# ev_ver_3.net
KiCad netlist of a schematic drawn in EAGLE
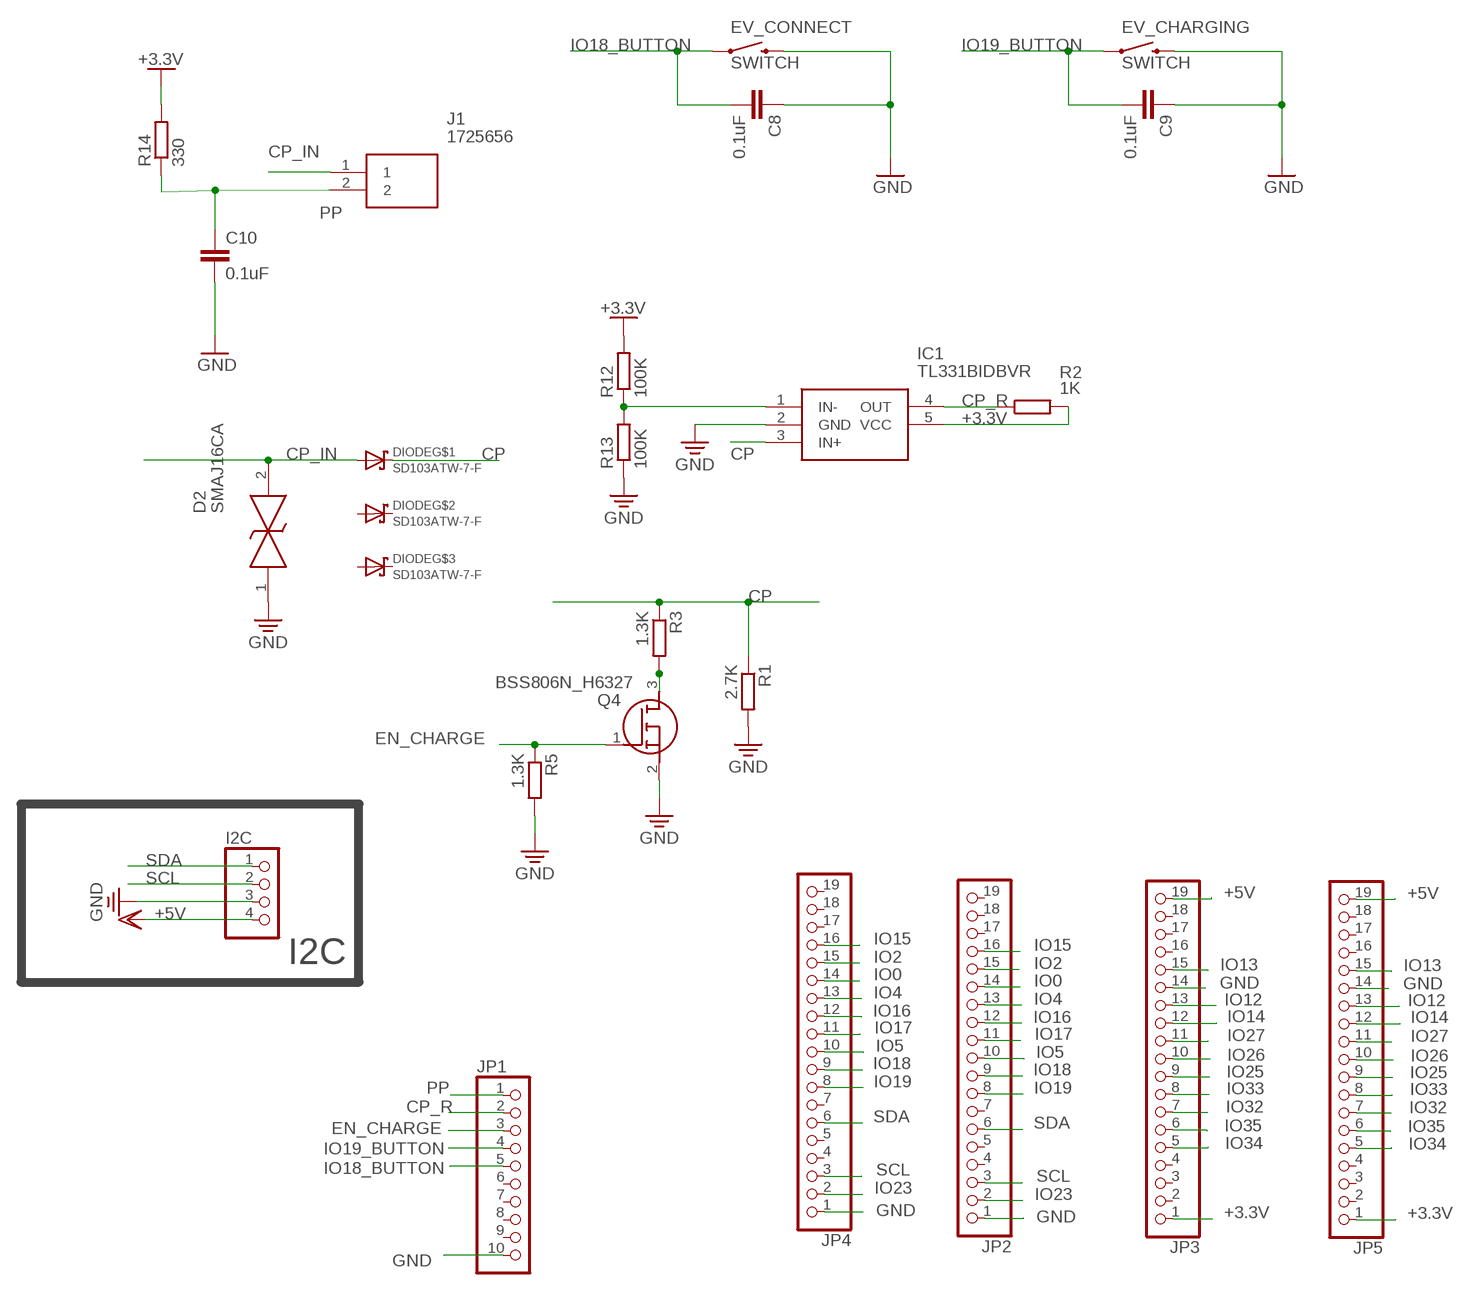
[diagram p0: schematic, sheet 1]

(export (version "E")
  (design (tool "Eeschema 10.0.6"))
  (components
    (comp (ref "C8")
      (value "0.1uF")
      (footprint "eagle-import:C0805")
      (libsource (lib "eagle-import") (part "C-EUC0805"))
    )
    (comp (ref "C9")
      (value "0.1uF")
      (footprint "eagle-import:C0805")
      (libsource (lib "eagle-import") (part "C-EUC0805"))
    )
    (comp (ref "C10")
      (value "0.1uF")
      (footprint "eagle-import:C0805")
      (libsource (lib "eagle-import") (part "C-EUC0805"))
    )
    (comp (ref "D2")
      (value "SMAJ16CA")
      (footprint "eagle-import:DIOM6626X229N")
      (fields (field (name "MOUSER_PART_NUMBER") "576-SMAJ16CA"))
      (libsource (lib "eagle-import") (part "SMAJ16CA"))
    )
    (comp (ref "DIODE")
      (value "SD103ATW-7-F")
      (footprint "eagle-import:SOT363")
      (fields (field (name "MF") "Diodes Inc."))
      (libsource (lib "eagle-import") (part "SD103ATW-7-F"))
    )
    (comp (ref "EV_CHARGING")
      (value "SWITCH")
      (footprint "eagle-import:SWITCH_2PIN")
      (libsource (lib "eagle-import") (part "SWITCH"))
    )
    (comp (ref "EV_CONNECT")
      (value "SWITCH")
      (footprint "eagle-import:SWITCH_2PIN")
      (libsource (lib "eagle-import") (part "SWITCH"))
    )
    (comp (ref "I2C")
      (value "PINHD-1X4")
      (footprint "eagle-import:1X04")
      (libsource (lib "eagle-import") (part "PINHD-1X4"))
    )
    (comp (ref "IC1")
      (value "TL331BIDBVR")
      (footprint "eagle-import:SOT95P280X145-5N")
      (fields (field (name "MOUSER_PART_NUMBER") "595-TL331BIDBVR"))
      (libsource (lib "eagle-import") (part "TL331BIDBVR"))
    )
    (comp (ref "J1")
      (value "1725656")
      (footprint "eagle-import:1725656")
      (fields (field (name "MOUSER_PART_NUMBER") "651-1725656"))
      (libsource (lib "eagle-import") (part "1725656"))
    )
    (comp (ref "JP1")
      (value "PINHD-1X10")
      (footprint "eagle-import:1X10")
      (libsource (lib "eagle-import") (part "PINHD-1X10"))
    )
    (comp (ref "JP2")
      (value "PINHD-1X19")
      (footprint "eagle-import:1X19")
      (libsource (lib "eagle-import") (part "PINHD-1X19"))
    )
    (comp (ref "JP3")
      (value "PINHD-1X19")
      (footprint "eagle-import:1X19")
      (libsource (lib "eagle-import") (part "PINHD-1X19"))
    )
    (comp (ref "JP4")
      (value "PINHD-1X19")
      (footprint "eagle-import:1X19")
      (libsource (lib "eagle-import") (part "PINHD-1X19"))
    )
    (comp (ref "JP5")
      (value "PINHD-1X19")
      (footprint "eagle-import:1X19")
      (libsource (lib "eagle-import") (part "PINHD-1X19"))
    )
    (comp (ref "Q4")
      (value "BSS806N_H6327")
      (footprint "eagle-import:SOT95P240X110-3N")
      (fields
        (field (name "MANUFACTURER_PART_NUMBER") "BSS806N H6327")
        (field (name "MOUSER_PART_NUMBER") "726-BSS806NH6327XT")
      )
      (libsource (lib "eagle-import") (part "BSS806N_H6327"))
    )
    (comp (ref "R1")
      (value "2.7K")
      (footprint "eagle-import:R0805")
      (libsource (lib "eagle-import") (part "R-EU_R0805"))
    )
    (comp (ref "R2")
      (value "1K")
      (footprint "eagle-import:R0805")
      (libsource (lib "eagle-import") (part "R-EU_R0805"))
    )
    (comp (ref "R3")
      (value "1.3K")
      (footprint "eagle-import:R0805")
      (libsource (lib "eagle-import") (part "R-EU_R0805"))
    )
    (comp (ref "R5")
      (value "1.3K")
      (footprint "eagle-import:R0805")
      (libsource (lib "eagle-import") (part "R-EU_R0805"))
    )
    (comp (ref "R12")
      (value "100K")
      (footprint "eagle-import:R0805")
      (libsource (lib "eagle-import") (part "R-EU_R0805"))
    )
    (comp (ref "R13")
      (value "100K")
      (footprint "eagle-import:R0805")
      (libsource (lib "eagle-import") (part "R-EU_R0805"))
    )
    (comp (ref "R14")
      (value "330")
      (footprint "eagle-import:R0805")
      (libsource (lib "eagle-import") (part "R-EU_R0805"))
    )
  )
  (nets
    (net (code "1") (name "+3.3V") (class "Default")
      (node (ref "IC1") (pin "5") (pinfunction "VCC_5") (pintype "bidirectional"))
      (node (ref "JP3") (pin "1") (pinfunction "1_1") (pintype "passive"))
      (node (ref "JP5") (pin "1") (pinfunction "1_1") (pintype "passive"))
      (node (ref "R12") (pin "2") (pinfunction "2_2") (pintype "passive"))
      (node (ref "R14") (pin "2") (pinfunction "2_2") (pintype "passive"))
      (node (ref "R2") (pin "2") (pinfunction "2_2") (pintype "passive"))
    )
    (net (code "2") (name "/CP") (class "Default")
      (node (ref "DIODE") (pin "1") (pinfunction "C_1") (pintype "passive"))
      (node (ref "IC1") (pin "3") (pinfunction "IN+_3") (pintype "bidirectional"))
      (node (ref "R1") (pin "1") (pinfunction "1_1") (pintype "passive"))
      (node (ref "R3") (pin "1") (pinfunction "1_1") (pintype "passive"))
    )
    (net (code "3") (name "/CP_IN") (class "Default")
      (node (ref "D2") (pin "2") (pinfunction "2_2") (pintype "bidirectional"))
      (node (ref "DIODE") (pin "6") (pinfunction "A_6") (pintype "passive"))
      (node (ref "J1") (pin "1") (pinfunction "1_1") (pintype "bidirectional"))
    )
    (net (code "4") (name "/CP_R") (class "Default")
      (node (ref "IC1") (pin "4") (pinfunction "OUT_4") (pintype "bidirectional"))
      (node (ref "JP1") (pin "2") (pinfunction "2_2") (pintype "passive"))
      (node (ref "R2") (pin "1") (pinfunction "1_1") (pintype "passive"))
    )
    (net (code "5") (name "/EN_CHARGE") (class "Default")
      (node (ref "JP1") (pin "3") (pinfunction "3_3") (pintype "passive"))
      (node (ref "Q4") (pin "1") (pinfunction "G_1") (pintype "bidirectional"))
      (node (ref "R5") (pin "1") (pinfunction "1_1") (pintype "passive"))
    )
    (net (code "6") (name "/IO0") (class "Default")
      (node (ref "JP2") (pin "14") (pinfunction "14_14") (pintype "passive"))
      (node (ref "JP4") (pin "14") (pinfunction "14_14") (pintype "passive"))
    )
    (net (code "7") (name "/IO2") (class "Default")
      (node (ref "JP2") (pin "15") (pinfunction "15_15") (pintype "passive"))
      (node (ref "JP4") (pin "15") (pinfunction "15_15") (pintype "passive"))
    )
    (net (code "8") (name "/IO4") (class "Default")
      (node (ref "JP2") (pin "13") (pinfunction "13_13") (pintype "passive"))
      (node (ref "JP4") (pin "13") (pinfunction "13_13") (pintype "passive"))
    )
    (net (code "9") (name "/IO5") (class "Default")
      (node (ref "JP2") (pin "10") (pinfunction "10_10") (pintype "passive"))
      (node (ref "JP4") (pin "10") (pinfunction "10_10") (pintype "passive"))
    )
    (net (code "10") (name "/IO12") (class "Default")
      (node (ref "JP3") (pin "13") (pinfunction "13_13") (pintype "passive"))
      (node (ref "JP5") (pin "13") (pinfunction "13_13") (pintype "passive"))
    )
    (net (code "11") (name "/IO13") (class "Default")
      (node (ref "JP3") (pin "15") (pinfunction "15_15") (pintype "passive"))
      (node (ref "JP5") (pin "15") (pinfunction "15_15") (pintype "passive"))
    )
    (net (code "12") (name "/IO14") (class "Default")
      (node (ref "JP3") (pin "12") (pinfunction "12_12") (pintype "passive"))
      (node (ref "JP5") (pin "12") (pinfunction "12_12") (pintype "passive"))
    )
    (net (code "13") (name "/IO15") (class "Default")
      (node (ref "JP2") (pin "16") (pinfunction "16_16") (pintype "passive"))
      (node (ref "JP4") (pin "16") (pinfunction "16_16") (pintype "passive"))
    )
    (net (code "14") (name "/IO16") (class "Default")
      (node (ref "JP2") (pin "12") (pinfunction "12_12") (pintype "passive"))
      (node (ref "JP4") (pin "12") (pinfunction "12_12") (pintype "passive"))
    )
    (net (code "15") (name "/IO17") (class "Default")
      (node (ref "JP2") (pin "11") (pinfunction "11_11") (pintype "passive"))
      (node (ref "JP4") (pin "11") (pinfunction "11_11") (pintype "passive"))
    )
    (net (code "16") (name "/IO18") (class "Default")
      (node (ref "JP2") (pin "9") (pinfunction "9_9") (pintype "passive"))
      (node (ref "JP4") (pin "9") (pinfunction "9_9") (pintype "passive"))
    )
    (net (code "17") (name "/IO18_BUTTON") (class "Default")
      (node (ref "C8") (pin "2") (pinfunction "2_2") (pintype "passive"))
      (node (ref "EV_CONNECT") (pin "1") (pinfunction "1_1") (pintype "passive"))
      (node (ref "JP1") (pin "5") (pinfunction "5_5") (pintype "passive"))
    )
    (net (code "18") (name "/IO19") (class "Default")
      (node (ref "JP2") (pin "8") (pinfunction "8_8") (pintype "passive"))
      (node (ref "JP4") (pin "8") (pinfunction "8_8") (pintype "passive"))
    )
    (net (code "19") (name "/IO19_BUTTON") (class "Default")
      (node (ref "C9") (pin "2") (pinfunction "2_2") (pintype "passive"))
      (node (ref "EV_CHARGING") (pin "1") (pinfunction "1_1") (pintype "passive"))
      (node (ref "JP1") (pin "4") (pinfunction "4_4") (pintype "passive"))
    )
    (net (code "20") (name "/IO23") (class "Default")
      (node (ref "JP2") (pin "2") (pinfunction "2_2") (pintype "passive"))
      (node (ref "JP4") (pin "2") (pinfunction "2_2") (pintype "passive"))
    )
    (net (code "21") (name "/IO25") (class "Default")
      (node (ref "JP3") (pin "9") (pinfunction "9_9") (pintype "passive"))
      (node (ref "JP5") (pin "9") (pinfunction "9_9") (pintype "passive"))
    )
    (net (code "22") (name "/IO26") (class "Default")
      (node (ref "JP3") (pin "10") (pinfunction "10_10") (pintype "passive"))
      (node (ref "JP5") (pin "10") (pinfunction "10_10") (pintype "passive"))
    )
    (net (code "23") (name "/IO27") (class "Default")
      (node (ref "JP3") (pin "11") (pinfunction "11_11") (pintype "passive"))
      (node (ref "JP5") (pin "11") (pinfunction "11_11") (pintype "passive"))
    )
    (net (code "24") (name "/IO32") (class "Default")
      (node (ref "JP3") (pin "7") (pinfunction "7_7") (pintype "passive"))
      (node (ref "JP5") (pin "7") (pinfunction "7_7") (pintype "passive"))
    )
    (net (code "25") (name "/IO33") (class "Default")
      (node (ref "JP3") (pin "8") (pinfunction "8_8") (pintype "passive"))
      (node (ref "JP5") (pin "8") (pinfunction "8_8") (pintype "passive"))
    )
    (net (code "26") (name "/IO34") (class "Default")
      (node (ref "JP3") (pin "5") (pinfunction "5_5") (pintype "passive"))
      (node (ref "JP5") (pin "5") (pinfunction "5_5") (pintype "passive"))
    )
    (net (code "27") (name "/IO35") (class "Default")
      (node (ref "JP3") (pin "6") (pinfunction "6_6") (pintype "passive"))
      (node (ref "JP5") (pin "6") (pinfunction "6_6") (pintype "passive"))
    )
    (net (code "28") (name "/PP") (class "Default")
      (node (ref "C10") (pin "1") (pinfunction "1_1") (pintype "passive"))
      (node (ref "J1") (pin "2") (pinfunction "2_2") (pintype "bidirectional"))
      (node (ref "JP1") (pin "1") (pinfunction "1_1") (pintype "passive"))
      (node (ref "R14") (pin "1") (pinfunction "1_1") (pintype "passive"))
    )
    (net (code "29") (name "/SCL") (class "Default")
      (node (ref "I2C") (pin "2") (pinfunction "2_2") (pintype "passive"))
      (node (ref "JP2") (pin "3") (pinfunction "3_3") (pintype "passive"))
      (node (ref "JP4") (pin "3") (pinfunction "3_3") (pintype "passive"))
    )
    (net (code "30") (name "/SDA") (class "Default")
      (node (ref "I2C") (pin "1") (pinfunction "1_1") (pintype "passive"))
      (node (ref "JP2") (pin "6") (pinfunction "6_6") (pintype "passive"))
      (node (ref "JP4") (pin "6") (pinfunction "6_6") (pintype "passive"))
    )
    (net (code "31") (name "GND") (class "Default")
      (node (ref "C10") (pin "2") (pinfunction "2_2") (pintype "passive"))
      (node (ref "C8") (pin "1") (pinfunction "1_1") (pintype "passive"))
      (node (ref "C9") (pin "1") (pinfunction "1_1") (pintype "passive"))
      (node (ref "D2") (pin "1") (pinfunction "1_1") (pintype "bidirectional"))
      (node (ref "EV_CHARGING") (pin "2") (pinfunction "2_2") (pintype "passive"))
      (node (ref "EV_CONNECT") (pin "2") (pinfunction "2_2") (pintype "passive"))
      (node (ref "I2C") (pin "3") (pinfunction "3_3") (pintype "passive"))
      (node (ref "IC1") (pin "2") (pinfunction "GND_2") (pintype "bidirectional"))
      (node (ref "JP1") (pin "10") (pinfunction "10_10") (pintype "passive"))
      (node (ref "JP2") (pin "1") (pinfunction "1_1") (pintype "passive"))
      (node (ref "JP3") (pin "14") (pinfunction "14_14") (pintype "passive"))
      (node (ref "JP4") (pin "1") (pinfunction "1_1") (pintype "passive"))
      (node (ref "JP5") (pin "14") (pinfunction "14_14") (pintype "passive"))
      (node (ref "Q4") (pin "2") (pinfunction "S_2") (pintype "bidirectional"))
      (node (ref "R1") (pin "2") (pinfunction "2_2") (pintype "passive"))
      (node (ref "R13") (pin "1") (pinfunction "1_1") (pintype "passive"))
      (node (ref "R5") (pin "2") (pinfunction "2_2") (pintype "passive"))
    )
    (net (code "32") (name "Net-(IC1-IN-)") (class "Default")
      (node (ref "IC1") (pin "1") (pinfunction "IN-_1") (pintype "bidirectional"))
      (node (ref "R12") (pin "1") (pinfunction "1_1") (pintype "passive"))
      (node (ref "R13") (pin "2") (pinfunction "2_2") (pintype "passive"))
    )
    (net (code "33") (name "Net-(Q4-D)") (class "Default")
      (node (ref "Q4") (pin "3") (pinfunction "D_3") (pintype "bidirectional"))
      (node (ref "R3") (pin "2") (pinfunction "2_2") (pintype "passive"))
    )
    (net (code "34") (name "VDD") (class "Default")
      (node (ref "I2C") (pin "4") (pinfunction "4_4") (pintype "passive"))
      (node (ref "JP3") (pin "19") (pinfunction "19_19") (pintype "passive"))
      (node (ref "JP5") (pin "19") (pinfunction "19_19") (pintype "passive"))
    )
    (net (code "35") (name "unconnected-(DIODEB-A-Pad5)") (class "Default")
      (node (ref "DIODE") (pin "5") (pinfunction "A_5") (pintype "passive"))
    )
    (net (code "36") (name "unconnected-(DIODEB-C-Pad2)") (class "Default")
      (node (ref "DIODE") (pin "2") (pinfunction "C_2") (pintype "passive"))
    )
    (net (code "37") (name "unconnected-(DIODEC-A-Pad4)") (class "Default")
      (node (ref "DIODE") (pin "4") (pinfunction "A_4") (pintype "passive"))
    )
    (net (code "38") (name "unconnected-(DIODEC-C-Pad3)") (class "Default")
      (node (ref "DIODE") (pin "3") (pinfunction "C_3") (pintype "passive"))
    )
    (net (code "39") (name "unconnected-(JP1-Pad6)") (class "Default")
      (node (ref "JP1") (pin "6") (pinfunction "6_6") (pintype "passive"))
    )
    (net (code "40") (name "unconnected-(JP1-Pad7)") (class "Default")
      (node (ref "JP1") (pin "7") (pinfunction "7_7") (pintype "passive"))
    )
    (net (code "41") (name "unconnected-(JP1-Pad8)") (class "Default")
      (node (ref "JP1") (pin "8") (pinfunction "8_8") (pintype "passive"))
    )
    (net (code "42") (name "unconnected-(JP1-Pad9)") (class "Default")
      (node (ref "JP1") (pin "9") (pinfunction "9_9") (pintype "passive"))
    )
    (net (code "43") (name "unconnected-(JP2-Pad4)") (class "Default")
      (node (ref "JP2") (pin "4") (pinfunction "4_4") (pintype "passive"))
    )
    (net (code "44") (name "unconnected-(JP2-Pad5)") (class "Default")
      (node (ref "JP2") (pin "5") (pinfunction "5_5") (pintype "passive"))
    )
    (net (code "45") (name "unconnected-(JP2-Pad7)") (class "Default")
      (node (ref "JP2") (pin "7") (pinfunction "7_7") (pintype "passive"))
    )
    (net (code "46") (name "unconnected-(JP2-Pad17)") (class "Default")
      (node (ref "JP2") (pin "17") (pinfunction "17_17") (pintype "passive"))
    )
    (net (code "47") (name "unconnected-(JP2-Pad18)") (class "Default")
      (node (ref "JP2") (pin "18") (pinfunction "18_18") (pintype "passive"))
    )
    (net (code "48") (name "unconnected-(JP2-Pad19)") (class "Default")
      (node (ref "JP2") (pin "19") (pinfunction "19_19") (pintype "passive"))
    )
    (net (code "49") (name "unconnected-(JP3-Pad2)") (class "Default")
      (node (ref "JP3") (pin "2") (pinfunction "2_2") (pintype "passive"))
    )
    (net (code "50") (name "unconnected-(JP3-Pad3)") (class "Default")
      (node (ref "JP3") (pin "3") (pinfunction "3_3") (pintype "passive"))
    )
    (net (code "51") (name "unconnected-(JP3-Pad4)") (class "Default")
      (node (ref "JP3") (pin "4") (pinfunction "4_4") (pintype "passive"))
    )
    (net (code "52") (name "unconnected-(JP3-Pad16)") (class "Default")
      (node (ref "JP3") (pin "16") (pinfunction "16_16") (pintype "passive"))
    )
    (net (code "53") (name "unconnected-(JP3-Pad17)") (class "Default")
      (node (ref "JP3") (pin "17") (pinfunction "17_17") (pintype "passive"))
    )
    (net (code "54") (name "unconnected-(JP3-Pad18)") (class "Default")
      (node (ref "JP3") (pin "18") (pinfunction "18_18") (pintype "passive"))
    )
    (net (code "55") (name "unconnected-(JP4-Pad4)") (class "Default")
      (node (ref "JP4") (pin "4") (pinfunction "4_4") (pintype "passive"))
    )
    (net (code "56") (name "unconnected-(JP4-Pad5)") (class "Default")
      (node (ref "JP4") (pin "5") (pinfunction "5_5") (pintype "passive"))
    )
    (net (code "57") (name "unconnected-(JP4-Pad7)") (class "Default")
      (node (ref "JP4") (pin "7") (pinfunction "7_7") (pintype "passive"))
    )
    (net (code "58") (name "unconnected-(JP4-Pad17)") (class "Default")
      (node (ref "JP4") (pin "17") (pinfunction "17_17") (pintype "passive"))
    )
    (net (code "59") (name "unconnected-(JP4-Pad18)") (class "Default")
      (node (ref "JP4") (pin "18") (pinfunction "18_18") (pintype "passive"))
    )
    (net (code "60") (name "unconnected-(JP4-Pad19)") (class "Default")
      (node (ref "JP4") (pin "19") (pinfunction "19_19") (pintype "passive"))
    )
    (net (code "61") (name "unconnected-(JP5-Pad2)") (class "Default")
      (node (ref "JP5") (pin "2") (pinfunction "2_2") (pintype "passive"))
    )
    (net (code "62") (name "unconnected-(JP5-Pad3)") (class "Default")
      (node (ref "JP5") (pin "3") (pinfunction "3_3") (pintype "passive"))
    )
    (net (code "63") (name "unconnected-(JP5-Pad4)") (class "Default")
      (node (ref "JP5") (pin "4") (pinfunction "4_4") (pintype "passive"))
    )
    (net (code "64") (name "unconnected-(JP5-Pad16)") (class "Default")
      (node (ref "JP5") (pin "16") (pinfunction "16_16") (pintype "passive"))
    )
    (net (code "65") (name "unconnected-(JP5-Pad17)") (class "Default")
      (node (ref "JP5") (pin "17") (pinfunction "17_17") (pintype "passive"))
    )
    (net (code "66") (name "unconnected-(JP5-Pad18)") (class "Default")
      (node (ref "JP5") (pin "18") (pinfunction "18_18") (pintype "passive"))
    )
  )
)
